# battery_monitor.net
KiCad netlist of a schematic drawn in EAGLE
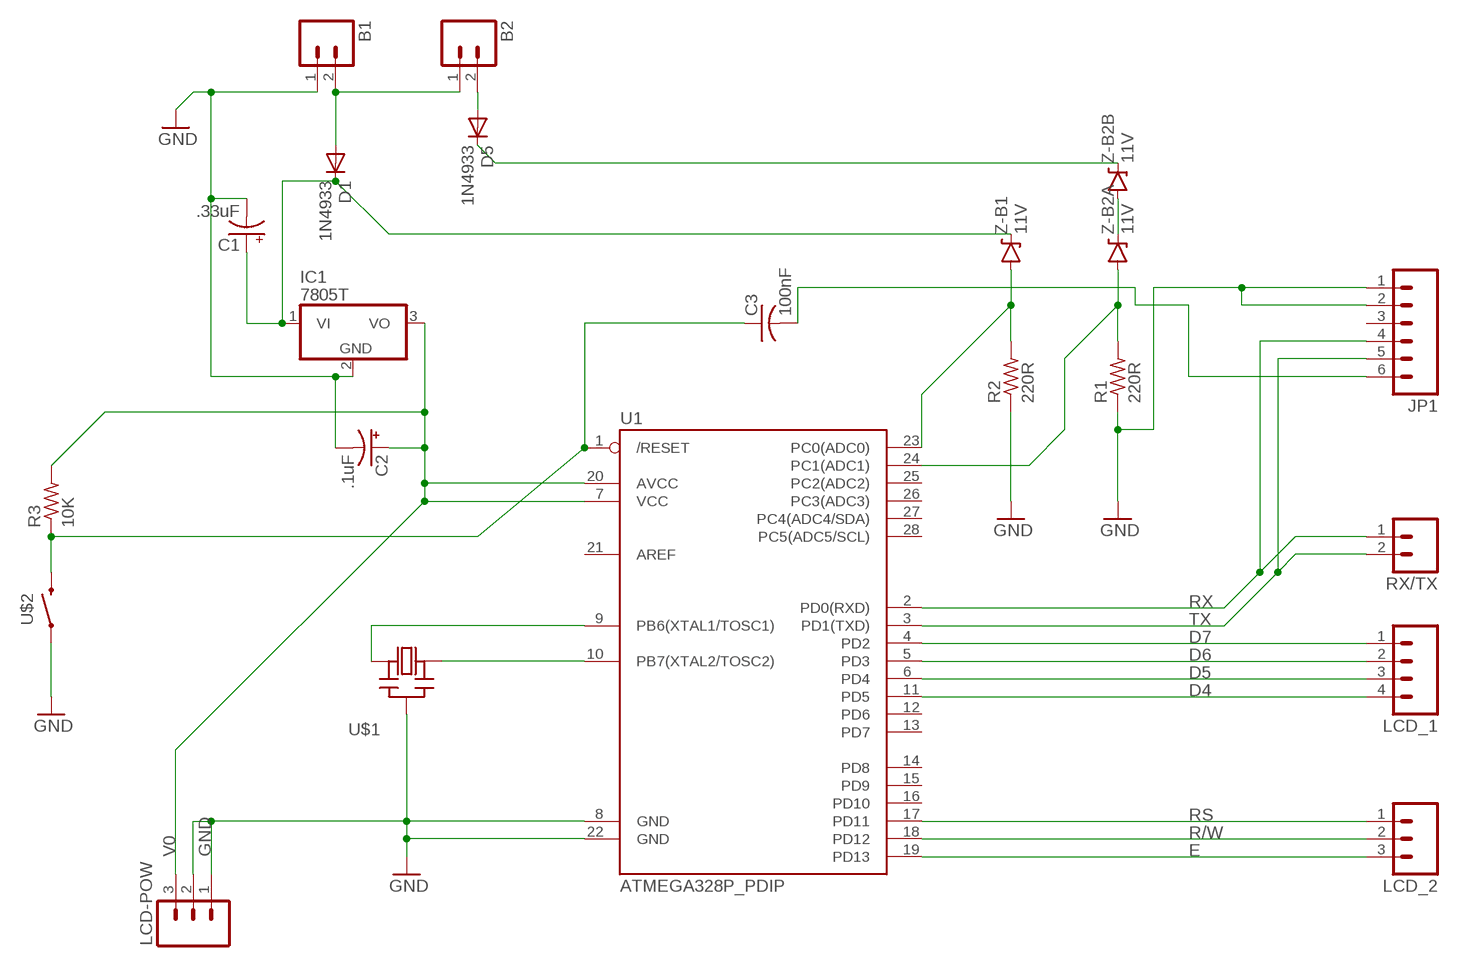
[diagram p0: schematic, sheet 1]

(export (version "E")
  (design (tool "Eeschema 10.0.6"))
  (components
    (comp (ref "B1")
      (value "2-HOLES2-HOLES-5.08MM")
      (footprint "eagle-import:2-HOLES_BIG")
      (libsource (lib "eagle-import") (part "2-HOLES2-HOLES-5.08MM"))
    )
    (comp (ref "B2")
      (value "2-HOLES2-HOLES-5.08MM")
      (footprint "eagle-import:2-HOLES_BIG")
      (libsource (lib "eagle-import") (part "2-HOLES2-HOLES-5.08MM"))
    )
    (comp (ref "C1")
      (value ".33uF")
      (footprint "eagle-import:E2,5-5")
      (libsource (lib "eagle-import") (part "CAPACITOR_POL"))
    )
    (comp (ref "C2")
      (value ".1uF")
      (footprint "eagle-import:E2,5-5")
      (libsource (lib "eagle-import") (part "CAPACITOR_POL"))
    )
    (comp (ref "C3")
      (value "100nF")
      (footprint "eagle-import:C050-025X075")
      (libsource (lib "eagle-import") (part "CAPACITOR050-025X075"))
    )
    (comp (ref "D1")
      (value "1N4933")
      (footprint "eagle-import:DO41-10")
      (libsource (lib "eagle-import") (part "1N4933"))
    )
    (comp (ref "D5")
      (value "1N4933")
      (footprint "eagle-import:DO41-10")
      (libsource (lib "eagle-import") (part "1N4933"))
    )
    (comp (ref "IC1")
      (value "7805T")
      (footprint "eagle-import:TO220H")
      (libsource (lib "eagle-import") (part "78T05"))
    )
    (comp (ref "JP1")
      (value "M06LONGPADS")
      (footprint "eagle-import:1X06_LONGPADS")
      (libsource (lib "eagle-import") (part "M06LONGPADS"))
    )
    (comp (ref "LCD-POW")
      (value "M03PTH")
      (footprint "eagle-import:1X03")
      (libsource (lib "eagle-import") (part "M03PTH"))
    )
    (comp (ref "LCD_1")
      (value "M04PTH")
      (footprint "eagle-import:1X04")
      (libsource (lib "eagle-import") (part "M04PTH"))
    )
    (comp (ref "LCD_2")
      (value "M03PTH")
      (footprint "eagle-import:1X03")
      (libsource (lib "eagle-import") (part "M03PTH"))
    )
    (comp (ref "R1")
      (value "220R")
      (footprint "eagle-import:0207_10")
      (libsource (lib "eagle-import") (part "RESISTOR0207/10"))
    )
    (comp (ref "R2")
      (value "220R")
      (footprint "eagle-import:0207_10")
      (libsource (lib "eagle-import") (part "RESISTOR0207/10"))
    )
    (comp (ref "R3")
      (value "10K")
      (footprint "eagle-import:0207_10")
      (libsource (lib "eagle-import") (part "RESISTOR0207/10"))
    )
    (comp (ref "RX/TX")
      (value "M02PTH")
      (footprint "eagle-import:1X02")
      (libsource (lib "eagle-import") (part "M02PTH"))
    )
    (comp (ref "U$1")
      (value "OSCILLATOR-THM")
      (footprint "eagle-import:CERM_OSC")
      (libsource (lib "eagle-import") (part "OSCILLATOR-THM"))
    )
    (comp (ref "U$2")
      (value "SWITCH-MOMENTARY4MM")
      (footprint "eagle-import:TACTILE_SWITCH_SMD")
      (libsource (lib "eagle-import") (part "SWITCH-MOMENTARY4MM"))
    )
    (comp (ref "U1")
      (value "ATMEGA328P_PDIP")
      (footprint "eagle-import:DIL28-3")
      (libsource (lib "eagle-import") (part "ATMEGA328P_PDIP"))
    )
    (comp (ref "Z-B1")
      (value "11V")
      (footprint "eagle-import:DIODE-ZENER")
      (libsource (lib "eagle-import") (part "DIODE-ZENERPTH"))
    )
    (comp (ref "Z-B2A")
      (value "11V")
      (footprint "eagle-import:DIODE-ZENER")
      (libsource (lib "eagle-import") (part "DIODE-ZENERPTH"))
    )
    (comp (ref "Z-B2B")
      (value "11V")
      (footprint "eagle-import:DIODE-ZENER")
      (libsource (lib "eagle-import") (part "DIODE-ZENERPTH"))
    )
  )
  (nets
    (net (code "1") (name "/D4") (class "Default")
      (node (ref "LCD_1") (pin "4") (pinfunction "4_4") (pintype "passive"))
      (node (ref "U1") (pin "11") (pinfunction "PD5_11") (pintype "bidirectional"))
    )
    (net (code "2") (name "/D5") (class "Default")
      (node (ref "LCD_1") (pin "3") (pinfunction "3_3") (pintype "passive"))
      (node (ref "U1") (pin "6") (pinfunction "PD4_6") (pintype "bidirectional"))
    )
    (net (code "3") (name "/D6") (class "Default")
      (node (ref "LCD_1") (pin "2") (pinfunction "2_2") (pintype "passive"))
      (node (ref "U1") (pin "5") (pinfunction "PD3_5") (pintype "bidirectional"))
    )
    (net (code "4") (name "/D7") (class "Default")
      (node (ref "LCD_1") (pin "1") (pinfunction "1_1") (pintype "passive"))
      (node (ref "U1") (pin "4") (pinfunction "PD2_4") (pintype "bidirectional"))
    )
    (net (code "5") (name "/E") (class "Default")
      (node (ref "LCD_2") (pin "3") (pinfunction "3_3") (pintype "passive"))
      (node (ref "U1") (pin "19") (pinfunction "PD13_19") (pintype "bidirectional"))
    )
    (net (code "6") (name "/RS") (class "Default")
      (node (ref "LCD_2") (pin "1") (pinfunction "1_1") (pintype "passive"))
      (node (ref "U1") (pin "17") (pinfunction "PD11_17") (pintype "bidirectional"))
    )
    (net (code "7") (name "/RX") (class "Default")
      (node (ref "JP1") (pin "4") (pinfunction "4_4") (pintype "passive"))
      (node (ref "RX/TX") (pin "1") (pinfunction "1_1") (pintype "passive"))
      (node (ref "U1") (pin "2") (pinfunction "PD0(RXD)_2") (pintype "bidirectional"))
    )
    (net (code "8") (name "/R{slash}W") (class "Default")
      (node (ref "LCD_2") (pin "2") (pinfunction "2_2") (pintype "passive"))
      (node (ref "U1") (pin "18") (pinfunction "PD12_18") (pintype "bidirectional"))
    )
    (net (code "9") (name "/TX") (class "Default")
      (node (ref "JP1") (pin "5") (pinfunction "5_5") (pintype "passive"))
      (node (ref "RX/TX") (pin "2") (pinfunction "2_2") (pintype "passive"))
      (node (ref "U1") (pin "3") (pinfunction "PD1(TXD)_3") (pintype "bidirectional"))
    )
    (net (code "10") (name "/V0") (class "Default")
      (node (ref "C2") (pin "+") (pinfunction "+_+") (pintype "passive"))
      (node (ref "IC1") (pin "3") (pinfunction "VO_3") (pintype "passive"))
      (node (ref "LCD-POW") (pin "3") (pinfunction "3_3") (pintype "passive"))
      (node (ref "R3") (pin "2") (pinfunction "2_2") (pintype "passive"))
      (node (ref "U1") (pin "20") (pinfunction "AVCC_20") (pintype "bidirectional"))
      (node (ref "U1") (pin "7") (pinfunction "VCC_7") (pintype "bidirectional"))
    )
    (net (code "11") (name "GND") (class "Default")
      (node (ref "B1") (pin "1") (pinfunction "1_1") (pintype "passive"))
      (node (ref "C1") (pin "-") (pinfunction "-_-") (pintype "passive"))
      (node (ref "C2") (pin "-") (pinfunction "-_-") (pintype "passive"))
      (node (ref "IC1") (pin "2") (pinfunction "GND_2") (pintype "passive"))
      (node (ref "JP1") (pin "1") (pinfunction "1_1") (pintype "passive"))
      (node (ref "JP1") (pin "2") (pinfunction "2_2") (pintype "passive"))
      (node (ref "LCD-POW") (pin "1") (pinfunction "1_1") (pintype "passive"))
      (node (ref "LCD-POW") (pin "2") (pinfunction "2_2") (pintype "passive"))
      (node (ref "R1") (pin "1") (pinfunction "1_1") (pintype "passive"))
      (node (ref "R2") (pin "1") (pinfunction "1_1") (pintype "passive"))
      (node (ref "U$1") (pin "P$2") (pinfunction "GND_P$2") (pintype "bidirectional"))
      (node (ref "U$2") (pin "1") (pinfunction "1_1") (pintype "passive"))
      (node (ref "U$2") (pin "2") (pinfunction "1_2") (pintype "passive"))
      (node (ref "U1") (pin "22") (pinfunction "GND_22") (pintype "bidirectional"))
      (node (ref "U1") (pin "8") (pinfunction "GND_8") (pintype "bidirectional"))
    )
    (net (code "12") (name "Net-(B1-Pad2)") (class "Default")
      (node (ref "B1") (pin "2") (pinfunction "2_2") (pintype "passive"))
      (node (ref "B2") (pin "1") (pinfunction "1_1") (pintype "passive"))
      (node (ref "D1") (pin "A") (pinfunction "A_A") (pintype "passive"))
    )
    (net (code "13") (name "Net-(B2-Pad2)") (class "Default")
      (node (ref "B2") (pin "2") (pinfunction "2_2") (pintype "passive"))
      (node (ref "D5") (pin "A") (pinfunction "A_A") (pintype "passive"))
    )
    (net (code "14") (name "Net-(C3-Pad2)") (class "Default")
      (node (ref "C3") (pin "2") (pinfunction "2_2") (pintype "passive"))
      (node (ref "JP1") (pin "6") (pinfunction "6_6") (pintype "passive"))
    )
    (net (code "15") (name "Net-(IC1-VI)") (class "Default")
      (node (ref "C1") (pin "+") (pinfunction "+_+") (pintype "passive"))
      (node (ref "D1") (pin "C") (pinfunction "C_C") (pintype "passive"))
      (node (ref "IC1") (pin "1") (pinfunction "VI_1") (pintype "input"))
      (node (ref "Z-B1") (pin "P$1") (pinfunction "C_P$1") (pintype "passive"))
    )
    (net (code "16") (name "Net-(U$1-IN)") (class "Default")
      (node (ref "U$1") (pin "P$1") (pinfunction "IN_P$1") (pintype "bidirectional"))
      (node (ref "U1") (pin "9") (pinfunction "PB6(XTAL1/TOSC1)_9") (pintype "bidirectional"))
    )
    (net (code "17") (name "Net-(U$1-OUT)") (class "Default")
      (node (ref "U$1") (pin "P$3") (pinfunction "OUT_P$3") (pintype "bidirectional"))
      (node (ref "U1") (pin "10") (pinfunction "PB7(XTAL2/TOSC2)_10") (pintype "bidirectional"))
    )
    (net (code "18") (name "Net-(U1-PC0(ADC0))") (class "Default")
      (node (ref "R2") (pin "2") (pinfunction "2_2") (pintype "passive"))
      (node (ref "U1") (pin "23") (pinfunction "PC0(ADC0)_23") (pintype "bidirectional"))
      (node (ref "Z-B1") (pin "P$2") (pinfunction "A_P$2") (pintype "passive"))
    )
    (net (code "19") (name "Net-(U1-PC1(ADC1))") (class "Default")
      (node (ref "R1") (pin "2") (pinfunction "2_2") (pintype "passive"))
      (node (ref "U1") (pin "24") (pinfunction "PC1(ADC1)_24") (pintype "bidirectional"))
      (node (ref "Z-B2A") (pin "P$2") (pinfunction "A_P$2") (pintype "passive"))
    )
    (net (code "20") (name "Net-(U1-{slash}RESET)") (class "Default")
      (node (ref "C3") (pin "1") (pinfunction "1_1") (pintype "passive"))
      (node (ref "R3") (pin "1") (pinfunction "1_1") (pintype "passive"))
      (node (ref "U$2") (pin "3") (pinfunction "2_3") (pintype "passive"))
      (node (ref "U$2") (pin "4") (pinfunction "2_4") (pintype "passive"))
      (node (ref "U1") (pin "1") (pinfunction "/RESET_1") (pintype "bidirectional"))
    )
    (net (code "21") (name "Net-(Z-B2A-C)") (class "Default")
      (node (ref "Z-B2A") (pin "P$1") (pinfunction "C_P$1") (pintype "passive"))
      (node (ref "Z-B2B") (pin "P$2") (pinfunction "A_P$2") (pintype "passive"))
    )
    (net (code "22") (name "Net-(Z-B2B-C)") (class "Default")
      (node (ref "D5") (pin "C") (pinfunction "C_C") (pintype "passive"))
      (node (ref "Z-B2B") (pin "P$1") (pinfunction "C_P$1") (pintype "passive"))
    )
    (net (code "23") (name "unconnected-(JP1-Pad3)") (class "Default")
      (node (ref "JP1") (pin "3") (pinfunction "3_3") (pintype "passive"))
    )
    (net (code "24") (name "unconnected-(U1-AREF-Pad21)") (class "Default")
      (node (ref "U1") (pin "21") (pinfunction "AREF_21") (pintype "bidirectional"))
    )
    (net (code "25") (name "unconnected-(U1-PC2(ADC2)-Pad25)") (class "Default")
      (node (ref "U1") (pin "25") (pinfunction "PC2(ADC2)_25") (pintype "bidirectional"))
    )
    (net (code "26") (name "unconnected-(U1-PC3(ADC3)-Pad26)") (class "Default")
      (node (ref "U1") (pin "26") (pinfunction "PC3(ADC3)_26") (pintype "bidirectional"))
    )
    (net (code "27") (name "unconnected-(U1-PC4(ADC4{slash}SDA)-Pad27)") (class "Default")
      (node (ref "U1") (pin "27") (pinfunction "PC4(ADC4/SDA)_27") (pintype "bidirectional"))
    )
    (net (code "28") (name "unconnected-(U1-PC5(ADC5{slash}SCL)-Pad28)") (class "Default")
      (node (ref "U1") (pin "28") (pinfunction "PC5(ADC5/SCL)_28") (pintype "bidirectional"))
    )
    (net (code "29") (name "unconnected-(U1-PD6-Pad12)") (class "Default")
      (node (ref "U1") (pin "12") (pinfunction "PD6_12") (pintype "bidirectional"))
    )
    (net (code "30") (name "unconnected-(U1-PD7-Pad13)") (class "Default")
      (node (ref "U1") (pin "13") (pinfunction "PD7_13") (pintype "bidirectional"))
    )
    (net (code "31") (name "unconnected-(U1-PD8-Pad14)") (class "Default")
      (node (ref "U1") (pin "14") (pinfunction "PD8_14") (pintype "bidirectional"))
    )
    (net (code "32") (name "unconnected-(U1-PD9-Pad15)") (class "Default")
      (node (ref "U1") (pin "15") (pinfunction "PD9_15") (pintype "bidirectional"))
    )
    (net (code "33") (name "unconnected-(U1-PD10-Pad16)") (class "Default")
      (node (ref "U1") (pin "16") (pinfunction "PD10_16") (pintype "bidirectional"))
    )
  )
)
